# NyanTimer-v5.net
KiCad netlist of a schematic drawn in EAGLE
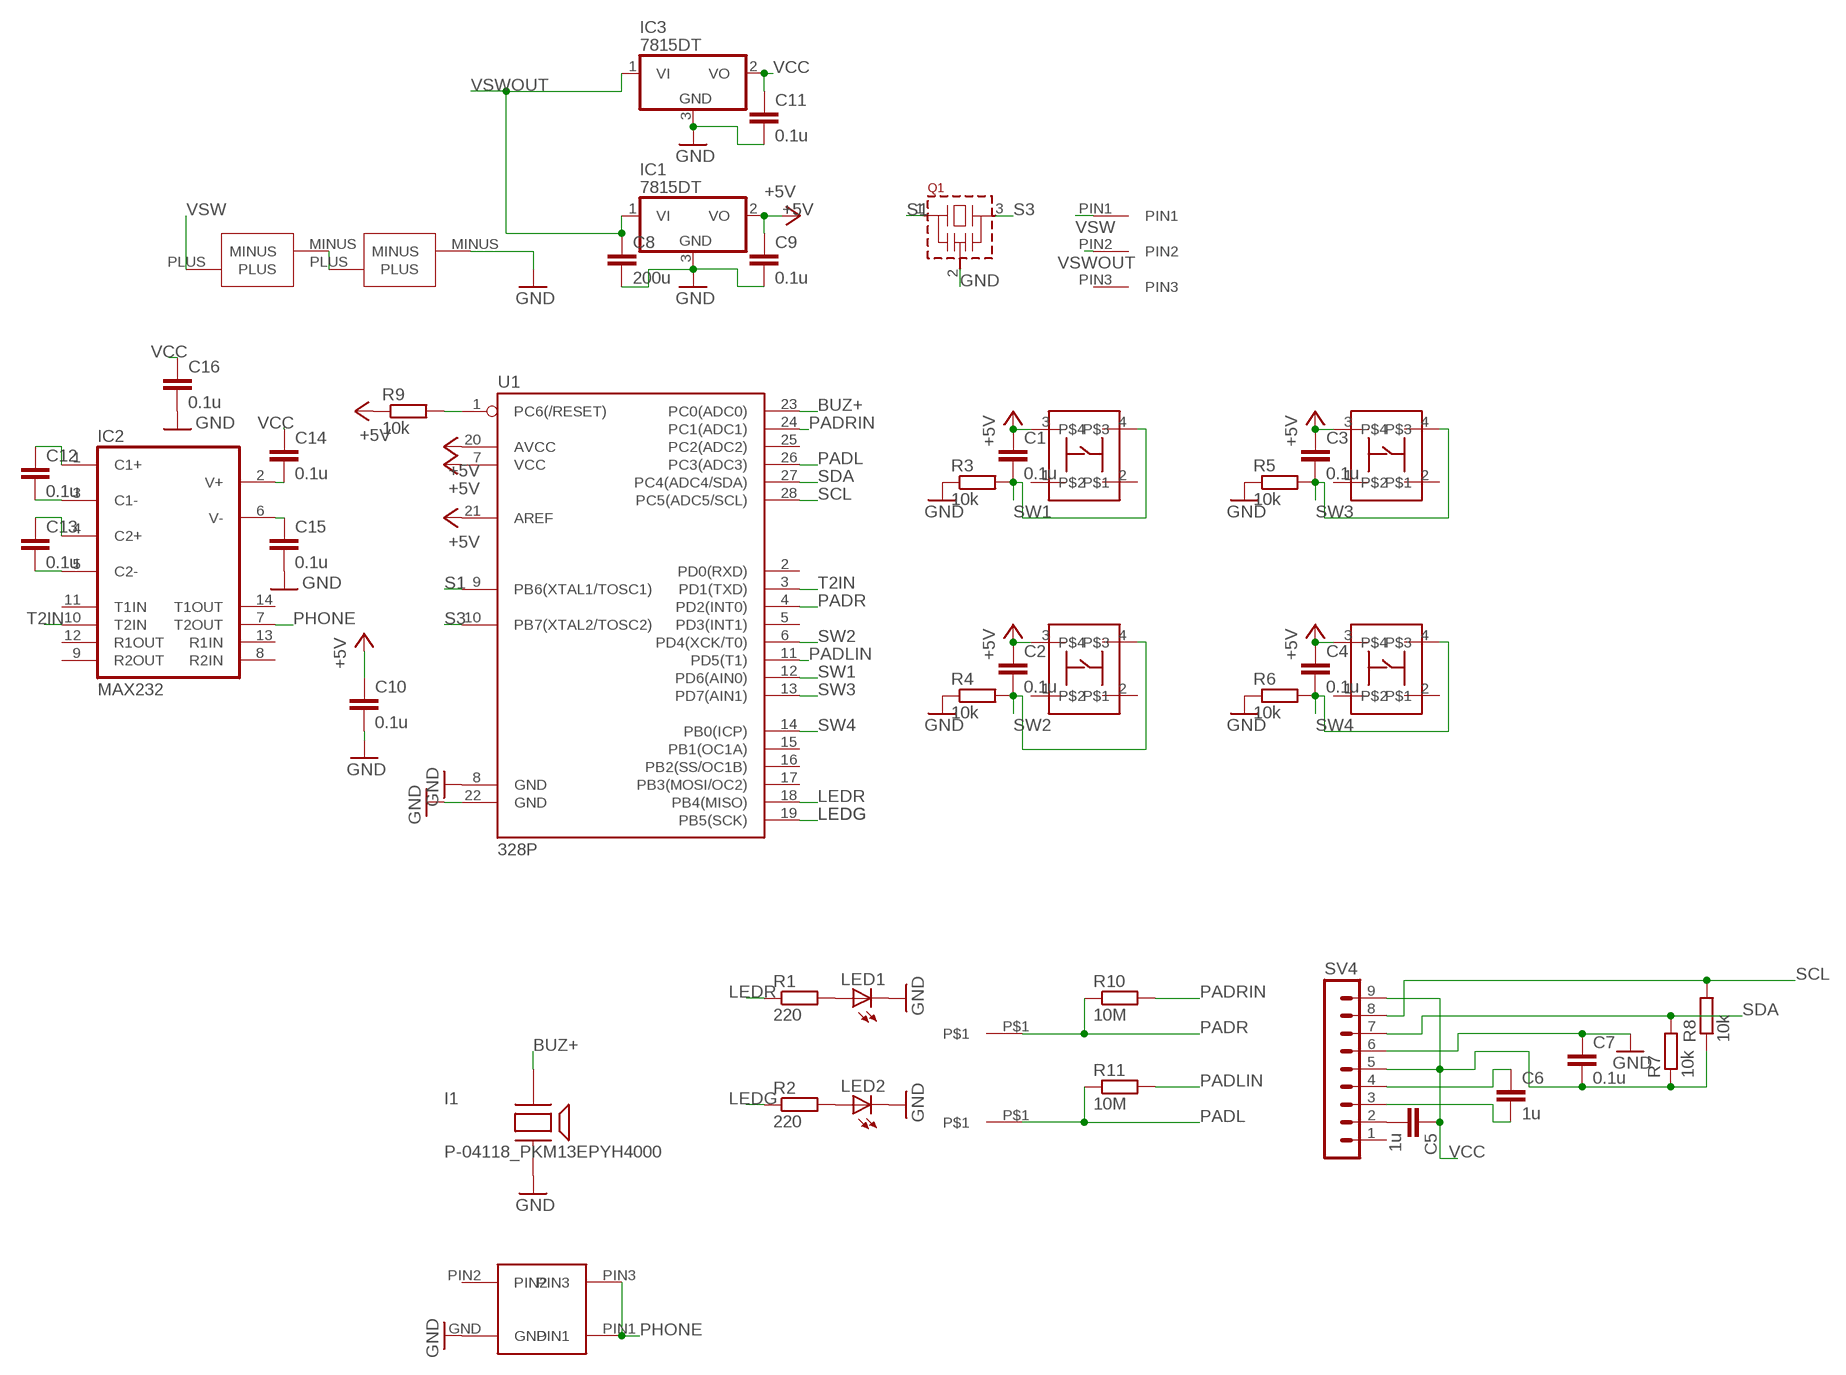
[diagram p0: schematic, sheet 1]

(export (version "E")
  (design (tool "Eeschema 10.0.6"))
  (components
    (comp (ref "BT1")
      (value "AKIZUKI_CR2032")
      (footprint "eagle-import:AKIZUKI_CR2032")
      (libsource (lib "eagle-import") (part "AKIZUKI_CR2032"))
    )
    (comp (ref "BT2")
      (value "AKIZUKI_CR2032")
      (footprint "eagle-import:AKIZUKI_CR2032")
      (libsource (lib "eagle-import") (part "AKIZUKI_CR2032"))
    )
    (comp (ref "C1")
      (value "0.1u")
      (footprint "eagle-import:C025-024X044")
      (libsource (lib "eagle-import") (part "C-EU025-024X044"))
    )
    (comp (ref "C2")
      (value "0.1u")
      (footprint "eagle-import:C025-024X044")
      (libsource (lib "eagle-import") (part "C-EU025-024X044"))
    )
    (comp (ref "C3")
      (value "0.1u")
      (footprint "eagle-import:C025-024X044")
      (libsource (lib "eagle-import") (part "C-EU025-024X044"))
    )
    (comp (ref "C4")
      (value "0.1u")
      (footprint "eagle-import:C025-024X044")
      (libsource (lib "eagle-import") (part "C-EU025-024X044"))
    )
    (comp (ref "C5")
      (value "1u")
      (footprint "eagle-import:C025-024X044")
      (libsource (lib "eagle-import") (part "C-EU025-024X044"))
    )
    (comp (ref "C6")
      (value "1u")
      (footprint "eagle-import:C025-024X044")
      (libsource (lib "eagle-import") (part "C-EU025-024X044"))
    )
    (comp (ref "C7")
      (value "0.1u")
      (footprint "eagle-import:C025-024X044")
      (libsource (lib "eagle-import") (part "C-EU025-024X044"))
    )
    (comp (ref "C8")
      (value "200u")
      (footprint "eagle-import:C025-024X044")
      (libsource (lib "eagle-import") (part "C-EU025-024X044"))
    )
    (comp (ref "C9")
      (value "0.1u")
      (footprint "eagle-import:C025-024X044")
      (libsource (lib "eagle-import") (part "C-EU025-024X044"))
    )
    (comp (ref "C10")
      (value "0.1u")
      (footprint "eagle-import:C025-024X044")
      (libsource (lib "eagle-import") (part "C-EU025-024X044"))
    )
    (comp (ref "C11")
      (value "0.1u")
      (footprint "eagle-import:C025-024X044")
      (libsource (lib "eagle-import") (part "C-EU025-024X044"))
    )
    (comp (ref "C12")
      (value "0.1u")
      (footprint "eagle-import:C025-024X044")
      (libsource (lib "eagle-import") (part "C-EU025-024X044"))
    )
    (comp (ref "C13")
      (value "0.1u")
      (footprint "eagle-import:C025-024X044")
      (libsource (lib "eagle-import") (part "C-EU025-024X044"))
    )
    (comp (ref "C14")
      (value "0.1u")
      (footprint "eagle-import:C025-024X044")
      (libsource (lib "eagle-import") (part "C-EU025-024X044"))
    )
    (comp (ref "C15")
      (value "0.1u")
      (footprint "eagle-import:C025-024X044")
      (libsource (lib "eagle-import") (part "C-EU025-024X044"))
    )
    (comp (ref "C16")
      (value "0.1u")
      (footprint "eagle-import:C025-024X044")
      (libsource (lib "eagle-import") (part "C-EU025-024X044"))
    )
    (comp (ref "CONNECTOR1")
      (value "TACT_SWITCH")
      (footprint "eagle-import:TACT_SWITCH")
      (libsource (lib "eagle-import") (part "TACT_SWITCH"))
    )
    (comp (ref "CONNECTOR2")
      (value "TACT_SWITCH")
      (footprint "eagle-import:TACT_SWITCH")
      (libsource (lib "eagle-import") (part "TACT_SWITCH"))
    )
    (comp (ref "CONNECTOR3")
      (value "TACT_SWITCH")
      (footprint "eagle-import:TACT_SWITCH")
      (libsource (lib "eagle-import") (part "TACT_SWITCH"))
    )
    (comp (ref "CONNECTOR4")
      (value "TACT_SWITCH")
      (footprint "eagle-import:TACT_SWITCH")
      (libsource (lib "eagle-import") (part "TACT_SWITCH"))
    )
    (comp (ref "I1")
      (value "P-04118_PKM13EPYH4000")
      (footprint "eagle-import:PKM13EPYH4000")
      (libsource (lib "eagle-import") (part "P-04118_PKM13EPYH4000"))
    )
    (comp (ref "IC1")
      (value "7815DT")
      (footprint "eagle-import:TO252")
      (libsource (lib "eagle-import") (part "78DT15"))
    )
    (comp (ref "IC2")
      (value "MAX232")
      (footprint "eagle-import:DIL16")
      (fields (field (name "MF") "MAXIM") (field (name "MPN") "MAX232ACPE+"))
      (libsource (lib "eagle-import") (part "MAX232"))
    )
    (comp (ref "IC3")
      (value "7815DT")
      (footprint "eagle-import:TO252")
      (libsource (lib "eagle-import") (part "78DT15"))
    )
    (comp (ref "LED1")
      (value "LED3MM")
      (footprint "eagle-import:LED3MM")
      (libsource (lib "eagle-import") (part "LED3MM"))
    )
    (comp (ref "LED2")
      (value "LED3MM")
      (footprint "eagle-import:LED3MM")
      (libsource (lib "eagle-import") (part "LED3MM"))
    )
    (comp (ref "PHN1")
      (value "PHONE")
      (footprint "eagle-import:PHONE")
      (libsource (lib "eagle-import") (part "PHONE"))
    )
    (comp (ref "PIN1")
      (value "1PINHEAD")
      (footprint "eagle-import:1PINHEAD")
      (libsource (lib "eagle-import") (part "1PINHEAD"))
    )
    (comp (ref "PIN2")
      (value "1PINHEAD")
      (footprint "eagle-import:1PINHEAD")
      (libsource (lib "eagle-import") (part "1PINHEAD"))
    )
    (comp (ref "Q1")
      (value "CSTLA_T")
      (footprint "eagle-import:CSTLA_T")
      (libsource (lib "eagle-import") (part "CSTLA_T"))
    )
    (comp (ref "R1")
      (value "220")
      (footprint "eagle-import:0207_10")
      (libsource (lib "eagle-import") (part "R-EU_0207/10"))
    )
    (comp (ref "R2")
      (value "220")
      (footprint "eagle-import:0207_10")
      (libsource (lib "eagle-import") (part "R-EU_0207/10"))
    )
    (comp (ref "R3")
      (value "10k")
      (footprint "eagle-import:0207_10")
      (libsource (lib "eagle-import") (part "R-EU_0207/10"))
    )
    (comp (ref "R4")
      (value "10k")
      (footprint "eagle-import:0207_10")
      (libsource (lib "eagle-import") (part "R-EU_0207/10"))
    )
    (comp (ref "R5")
      (value "10k")
      (footprint "eagle-import:0207_10")
      (libsource (lib "eagle-import") (part "R-EU_0207/10"))
    )
    (comp (ref "R6")
      (value "10k")
      (footprint "eagle-import:0207_10")
      (libsource (lib "eagle-import") (part "R-EU_0207/10"))
    )
    (comp (ref "R7")
      (value "10k")
      (footprint "eagle-import:0207_10")
      (libsource (lib "eagle-import") (part "R-EU_0207/10"))
    )
    (comp (ref "R8")
      (value "10k")
      (footprint "eagle-import:0207_10")
      (libsource (lib "eagle-import") (part "R-EU_0207/10"))
    )
    (comp (ref "R9")
      (value "10k")
      (footprint "eagle-import:0207_10")
      (libsource (lib "eagle-import") (part "R-EU_0207/10"))
    )
    (comp (ref "R10")
      (value "10M")
      (footprint "eagle-import:0207_10")
      (libsource (lib "eagle-import") (part "R-EU_0207/10"))
    )
    (comp (ref "R11")
      (value "10M")
      (footprint "eagle-import:0207_10")
      (libsource (lib "eagle-import") (part "R-EU_0207/10"))
    )
    (comp (ref "SV4")
      (value "MA09-1")
      (footprint "eagle-import:MA09-1")
      (libsource (lib "eagle-import") (part "MA09-1"))
    )
    (comp (ref "SW1")
      (value "AKIZUKI_SWITCH")
      (footprint "eagle-import:AKIZUKI_SWITCH")
      (libsource (lib "eagle-import") (part "AKIZUKI_SWITCH"))
    )
    (comp (ref "U1")
      (value "328P")
      (footprint "eagle-import:DIP28")
      (libsource (lib "eagle-import") (part "ATMEGA328P_PDIP"))
    )
  )
  (nets
    (net (code "1") (name "+5V") (class "Default")
      (node (ref "C1") (pin "1") (pinfunction "1_1") (pintype "passive"))
      (node (ref "C10") (pin "1") (pinfunction "1_1") (pintype "passive"))
      (node (ref "C2") (pin "1") (pinfunction "1_1") (pintype "passive"))
      (node (ref "C3") (pin "1") (pinfunction "1_1") (pintype "passive"))
      (node (ref "C4") (pin "1") (pinfunction "1_1") (pintype "passive"))
      (node (ref "C9") (pin "1") (pinfunction "1_1") (pintype "passive"))
      (node (ref "CONNECTOR1") (pin "3") (pinfunction "P$3_3") (pintype "bidirectional"))
      (node (ref "CONNECTOR2") (pin "3") (pinfunction "P$3_3") (pintype "bidirectional"))
      (node (ref "CONNECTOR3") (pin "3") (pinfunction "P$3_3") (pintype "bidirectional"))
      (node (ref "CONNECTOR4") (pin "3") (pinfunction "P$3_3") (pintype "bidirectional"))
      (node (ref "IC1") (pin "2") (pinfunction "VO_2") (pintype "passive"))
      (node (ref "R9") (pin "1") (pinfunction "1_1") (pintype "passive"))
      (node (ref "U1") (pin "20") (pinfunction "AVCC_20") (pintype "bidirectional"))
      (node (ref "U1") (pin "21") (pinfunction "AREF_21") (pintype "bidirectional"))
      (node (ref "U1") (pin "7") (pinfunction "VCC_7") (pintype "bidirectional"))
    )
    (net (code "2") (name "/BUZ+") (class "Default")
      (node (ref "I1") (pin "1") (pinfunction "1_1") (pintype "bidirectional"))
      (node (ref "U1") (pin "23") (pinfunction "PC0(ADC0)_23") (pintype "bidirectional"))
    )
    (net (code "3") (name "/LEDG") (class "Default")
      (node (ref "R2") (pin "1") (pinfunction "1_1") (pintype "passive"))
      (node (ref "U1") (pin "19") (pinfunction "PB5(SCK)_19") (pintype "bidirectional"))
    )
    (net (code "4") (name "/LEDR") (class "Default")
      (node (ref "R1") (pin "1") (pinfunction "1_1") (pintype "passive"))
      (node (ref "U1") (pin "18") (pinfunction "PB4(MISO)_18") (pintype "bidirectional"))
    )
    (net (code "5") (name "/PADL") (class "Default")
      (node (ref "PIN1") (pin "P$1") (pinfunction "P$1_P$1") (pintype "bidirectional"))
      (node (ref "R11") (pin "1") (pinfunction "1_1") (pintype "passive"))
      (node (ref "U1") (pin "26") (pinfunction "PC3(ADC3)_26") (pintype "bidirectional"))
    )
    (net (code "6") (name "/PADLIN") (class "Default")
      (node (ref "R11") (pin "2") (pinfunction "2_2") (pintype "passive"))
      (node (ref "U1") (pin "11") (pinfunction "PD5(T1)_11") (pintype "bidirectional"))
    )
    (net (code "7") (name "/PADR") (class "Default")
      (node (ref "PIN2") (pin "P$1") (pinfunction "P$1_P$1") (pintype "bidirectional"))
      (node (ref "R10") (pin "1") (pinfunction "1_1") (pintype "passive"))
      (node (ref "U1") (pin "4") (pinfunction "PD2(INT0)_4") (pintype "bidirectional"))
    )
    (net (code "8") (name "/PADRIN") (class "Default")
      (node (ref "R10") (pin "2") (pinfunction "2_2") (pintype "passive"))
      (node (ref "U1") (pin "24") (pinfunction "PC1(ADC1)_24") (pintype "bidirectional"))
    )
    (net (code "9") (name "/PHONE") (class "Default")
      (node (ref "IC2") (pin "7") (pinfunction "T2OUT_7") (pintype "output"))
      (node (ref "PHN1") (pin "PIN1") (pinfunction "PIN1_PIN1") (pintype "bidirectional"))
      (node (ref "PHN1") (pin "PIN3") (pinfunction "PIN3_PIN3") (pintype "bidirectional"))
    )
    (net (code "10") (name "/S1") (class "Default")
      (node (ref "Q1") (pin "1") (pinfunction "1_1") (pintype "output"))
      (node (ref "U1") (pin "9") (pinfunction "PB6(XTAL1/TOSC1)_9") (pintype "bidirectional"))
    )
    (net (code "11") (name "/S3") (class "Default")
      (node (ref "Q1") (pin "3") (pinfunction "3_3") (pintype "input"))
      (node (ref "U1") (pin "10") (pinfunction "PB7(XTAL2/TOSC2)_10") (pintype "bidirectional"))
    )
    (net (code "12") (name "/SCL") (class "Default")
      (node (ref "R8") (pin "2") (pinfunction "2_2") (pintype "passive"))
      (node (ref "SV4") (pin "8") (pinfunction "8_8") (pintype "passive"))
      (node (ref "U1") (pin "28") (pinfunction "PC5(ADC5/SCL)_28") (pintype "bidirectional"))
    )
    (net (code "13") (name "/SDA") (class "Default")
      (node (ref "R7") (pin "2") (pinfunction "2_2") (pintype "passive"))
      (node (ref "SV4") (pin "7") (pinfunction "7_7") (pintype "passive"))
      (node (ref "U1") (pin "27") (pinfunction "PC4(ADC4/SDA)_27") (pintype "bidirectional"))
    )
    (net (code "14") (name "/SW1") (class "Default")
      (node (ref "C1") (pin "2") (pinfunction "2_2") (pintype "passive"))
      (node (ref "CONNECTOR1") (pin "4") (pinfunction "P$4_4") (pintype "bidirectional"))
      (node (ref "R3") (pin "2") (pinfunction "2_2") (pintype "passive"))
      (node (ref "U1") (pin "12") (pinfunction "PD6(AIN0)_12") (pintype "bidirectional"))
    )
    (net (code "15") (name "/SW2") (class "Default")
      (node (ref "C2") (pin "2") (pinfunction "2_2") (pintype "passive"))
      (node (ref "CONNECTOR2") (pin "4") (pinfunction "P$4_4") (pintype "bidirectional"))
      (node (ref "R4") (pin "2") (pinfunction "2_2") (pintype "passive"))
      (node (ref "U1") (pin "6") (pinfunction "PD4(XCK/T0)_6") (pintype "bidirectional"))
    )
    (net (code "16") (name "/SW3") (class "Default")
      (node (ref "C3") (pin "2") (pinfunction "2_2") (pintype "passive"))
      (node (ref "CONNECTOR3") (pin "4") (pinfunction "P$4_4") (pintype "bidirectional"))
      (node (ref "R5") (pin "2") (pinfunction "2_2") (pintype "passive"))
      (node (ref "U1") (pin "13") (pinfunction "PD7(AIN1)_13") (pintype "bidirectional"))
    )
    (net (code "17") (name "/SW4") (class "Default")
      (node (ref "C4") (pin "2") (pinfunction "2_2") (pintype "passive"))
      (node (ref "CONNECTOR4") (pin "4") (pinfunction "P$4_4") (pintype "bidirectional"))
      (node (ref "R6") (pin "2") (pinfunction "2_2") (pintype "passive"))
      (node (ref "U1") (pin "14") (pinfunction "PB0(ICP)_14") (pintype "bidirectional"))
    )
    (net (code "18") (name "/T2IN") (class "Default")
      (node (ref "IC2") (pin "10") (pinfunction "T2IN_10") (pintype "input"))
      (node (ref "U1") (pin "3") (pinfunction "PD1(TXD)_3") (pintype "bidirectional"))
    )
    (net (code "19") (name "/VCC") (class "Default")
      (node (ref "C11") (pin "1") (pinfunction "1_1") (pintype "passive"))
      (node (ref "C14") (pin "1") (pinfunction "1_1") (pintype "passive"))
      (node (ref "C16") (pin "1") (pinfunction "1_1") (pintype "passive"))
      (node (ref "C5") (pin "1") (pinfunction "1_1") (pintype "passive"))
      (node (ref "C7") (pin "2") (pinfunction "2_2") (pintype "passive"))
      (node (ref "IC3") (pin "2") (pinfunction "VO_2") (pintype "passive"))
      (node (ref "R7") (pin "1") (pinfunction "1_1") (pintype "passive"))
      (node (ref "R8") (pin "1") (pinfunction "1_1") (pintype "passive"))
      (node (ref "SV4") (pin "5") (pinfunction "5_5") (pintype "passive"))
      (node (ref "SV4") (pin "9") (pinfunction "9_9") (pintype "passive"))
    )
    (net (code "20") (name "/VSW") (class "Default")
      (node (ref "BT1") (pin "PLUS") (pinfunction "PLUS_PLUS") (pintype "bidirectional"))
      (node (ref "SW1") (pin "PIN1") (pinfunction "PIN1_PIN1") (pintype "bidirectional"))
    )
    (net (code "21") (name "/VSWOUT") (class "Default")
      (node (ref "C8") (pin "1") (pinfunction "1_1") (pintype "passive"))
      (node (ref "IC1") (pin "1") (pinfunction "VI_1") (pintype "input"))
      (node (ref "IC3") (pin "1") (pinfunction "VI_1") (pintype "input"))
      (node (ref "SW1") (pin "PIN2") (pinfunction "PIN2_PIN2") (pintype "bidirectional"))
    )
    (net (code "22") (name "GND") (class "Default")
      (node (ref "BT2") (pin "MINUS") (pinfunction "MINUS_MINUS") (pintype "bidirectional"))
      (node (ref "C10") (pin "2") (pinfunction "2_2") (pintype "passive"))
      (node (ref "C11") (pin "2") (pinfunction "2_2") (pintype "passive"))
      (node (ref "C15") (pin "2") (pinfunction "2_2") (pintype "passive"))
      (node (ref "C16") (pin "2") (pinfunction "2_2") (pintype "passive"))
      (node (ref "C7") (pin "1") (pinfunction "1_1") (pintype "passive"))
      (node (ref "C8") (pin "2") (pinfunction "2_2") (pintype "passive"))
      (node (ref "C9") (pin "2") (pinfunction "2_2") (pintype "passive"))
      (node (ref "I1") (pin "2") (pinfunction "2_2") (pintype "bidirectional"))
      (node (ref "IC1") (pin "3") (pinfunction "GND_3") (pintype "passive"))
      (node (ref "IC3") (pin "3") (pinfunction "GND_3") (pintype "passive"))
      (node (ref "LED1") (pin "K") (pinfunction "C_K") (pintype "passive"))
      (node (ref "LED2") (pin "K") (pinfunction "C_K") (pintype "passive"))
      (node (ref "PHN1") (pin "GND") (pinfunction "GND_GND") (pintype "bidirectional"))
      (node (ref "Q1") (pin "2") (pinfunction "VSS_2") (pintype "power_in"))
      (node (ref "R3") (pin "1") (pinfunction "1_1") (pintype "passive"))
      (node (ref "R4") (pin "1") (pinfunction "1_1") (pintype "passive"))
      (node (ref "R5") (pin "1") (pinfunction "1_1") (pintype "passive"))
      (node (ref "R6") (pin "1") (pinfunction "1_1") (pintype "passive"))
      (node (ref "SV4") (pin "6") (pinfunction "6_6") (pintype "passive"))
      (node (ref "U1") (pin "22") (pinfunction "GND_22") (pintype "bidirectional"))
      (node (ref "U1") (pin "8") (pinfunction "GND_8") (pintype "bidirectional"))
    )
    (net (code "23") (name "Net-(BT1-PadMINUS)") (class "Default")
      (node (ref "BT1") (pin "MINUS") (pinfunction "MINUS_MINUS") (pintype "bidirectional"))
      (node (ref "BT2") (pin "PLUS") (pinfunction "PLUS_PLUS") (pintype "bidirectional"))
    )
    (net (code "24") (name "Net-(C5-Pad2)") (class "Default")
      (node (ref "C5") (pin "2") (pinfunction "2_2") (pintype "passive"))
      (node (ref "SV4") (pin "2") (pinfunction "2_2") (pintype "passive"))
    )
    (net (code "25") (name "Net-(C6-Pad1)") (class "Default")
      (node (ref "C6") (pin "1") (pinfunction "1_1") (pintype "passive"))
      (node (ref "SV4") (pin "4") (pinfunction "4_4") (pintype "passive"))
    )
    (net (code "26") (name "Net-(C6-Pad2)") (class "Default")
      (node (ref "C6") (pin "2") (pinfunction "2_2") (pintype "passive"))
      (node (ref "SV4") (pin "3") (pinfunction "3_3") (pintype "passive"))
    )
    (net (code "27") (name "Net-(IC2A-C1+)") (class "Default")
      (node (ref "C12") (pin "1") (pinfunction "1_1") (pintype "passive"))
      (node (ref "IC2") (pin "1") (pinfunction "C1+_1") (pintype "bidirectional"))
    )
    (net (code "28") (name "Net-(IC2A-C1-)") (class "Default")
      (node (ref "C12") (pin "2") (pinfunction "2_2") (pintype "passive"))
      (node (ref "IC2") (pin "3") (pinfunction "C1-_3") (pintype "bidirectional"))
    )
    (net (code "29") (name "Net-(IC2A-C2+)") (class "Default")
      (node (ref "C13") (pin "1") (pinfunction "1_1") (pintype "passive"))
      (node (ref "IC2") (pin "4") (pinfunction "C2+_4") (pintype "bidirectional"))
    )
    (net (code "30") (name "Net-(IC2A-C2-)") (class "Default")
      (node (ref "C13") (pin "2") (pinfunction "2_2") (pintype "passive"))
      (node (ref "IC2") (pin "5") (pinfunction "C2-_5") (pintype "bidirectional"))
    )
    (net (code "31") (name "Net-(IC2A-V+)") (class "Default")
      (node (ref "C14") (pin "2") (pinfunction "2_2") (pintype "passive"))
      (node (ref "IC2") (pin "2") (pinfunction "V+_2") (pintype "bidirectional"))
    )
    (net (code "32") (name "Net-(IC2A-V-)") (class "Default")
      (node (ref "C15") (pin "1") (pinfunction "1_1") (pintype "passive"))
      (node (ref "IC2") (pin "6") (pinfunction "V-_6") (pintype "bidirectional"))
    )
    (net (code "33") (name "Net-(LED1-PadA)") (class "Default")
      (node (ref "LED1") (pin "A") (pinfunction "A_A") (pintype "passive"))
      (node (ref "R1") (pin "2") (pinfunction "2_2") (pintype "passive"))
    )
    (net (code "34") (name "Net-(LED2-PadA)") (class "Default")
      (node (ref "LED2") (pin "A") (pinfunction "A_A") (pintype "passive"))
      (node (ref "R2") (pin "2") (pinfunction "2_2") (pintype "passive"))
    )
    (net (code "35") (name "Net-(U1-PC6({slash}RESET))") (class "Default")
      (node (ref "R9") (pin "2") (pinfunction "2_2") (pintype "passive"))
      (node (ref "U1") (pin "1") (pinfunction "PC6(/RESET)_1") (pintype "bidirectional"))
    )
    (net (code "36") (name "unconnected-(CONNECTOR1-P$1-Pad1)") (class "Default")
      (node (ref "CONNECTOR1") (pin "1") (pinfunction "P$1_1") (pintype "bidirectional"))
    )
    (net (code "37") (name "unconnected-(CONNECTOR1-P$2-Pad2)") (class "Default")
      (node (ref "CONNECTOR1") (pin "2") (pinfunction "P$2_2") (pintype "bidirectional"))
    )
    (net (code "38") (name "unconnected-(CONNECTOR2-P$1-Pad1)") (class "Default")
      (node (ref "CONNECTOR2") (pin "1") (pinfunction "P$1_1") (pintype "bidirectional"))
    )
    (net (code "39") (name "unconnected-(CONNECTOR2-P$2-Pad2)") (class "Default")
      (node (ref "CONNECTOR2") (pin "2") (pinfunction "P$2_2") (pintype "bidirectional"))
    )
    (net (code "40") (name "unconnected-(CONNECTOR3-P$1-Pad1)") (class "Default")
      (node (ref "CONNECTOR3") (pin "1") (pinfunction "P$1_1") (pintype "bidirectional"))
    )
    (net (code "41") (name "unconnected-(CONNECTOR3-P$2-Pad2)") (class "Default")
      (node (ref "CONNECTOR3") (pin "2") (pinfunction "P$2_2") (pintype "bidirectional"))
    )
    (net (code "42") (name "unconnected-(CONNECTOR4-P$1-Pad1)") (class "Default")
      (node (ref "CONNECTOR4") (pin "1") (pinfunction "P$1_1") (pintype "bidirectional"))
    )
    (net (code "43") (name "unconnected-(CONNECTOR4-P$2-Pad2)") (class "Default")
      (node (ref "CONNECTOR4") (pin "2") (pinfunction "P$2_2") (pintype "bidirectional"))
    )
    (net (code "44") (name "unconnected-(IC2A-R1IN-Pad13)") (class "Default")
      (node (ref "IC2") (pin "13") (pinfunction "R1IN_13") (pintype "input"))
    )
    (net (code "45") (name "unconnected-(IC2A-R1OUT-Pad12)") (class "Default")
      (node (ref "IC2") (pin "12") (pinfunction "R1OUT_12") (pintype "output"))
    )
    (net (code "46") (name "unconnected-(IC2A-R2IN-Pad8)") (class "Default")
      (node (ref "IC2") (pin "8") (pinfunction "R2IN_8") (pintype "input"))
    )
    (net (code "47") (name "unconnected-(IC2A-R2OUT-Pad9)") (class "Default")
      (node (ref "IC2") (pin "9") (pinfunction "R2OUT_9") (pintype "output"))
    )
    (net (code "48") (name "unconnected-(IC2A-T1IN-Pad11)") (class "Default")
      (node (ref "IC2") (pin "11") (pinfunction "T1IN_11") (pintype "input"))
    )
    (net (code "49") (name "unconnected-(IC2A-T1OUT-Pad14)") (class "Default")
      (node (ref "IC2") (pin "14") (pinfunction "T1OUT_14") (pintype "output"))
    )
    (net (code "50") (name "unconnected-(PHN1-PadPIN2)") (class "Default")
      (node (ref "PHN1") (pin "PIN2") (pinfunction "PIN2_PIN2") (pintype "bidirectional"))
    )
    (net (code "51") (name "unconnected-(SV4-Pad1)") (class "Default")
      (node (ref "SV4") (pin "1") (pinfunction "1_1") (pintype "passive"))
    )
    (net (code "52") (name "unconnected-(SW1-PadPIN3)") (class "Default")
      (node (ref "SW1") (pin "PIN3") (pinfunction "PIN3_PIN3") (pintype "bidirectional"))
    )
    (net (code "53") (name "unconnected-(U1-PB1(OC1A)-Pad15)") (class "Default")
      (node (ref "U1") (pin "15") (pinfunction "PB1(OC1A)_15") (pintype "bidirectional"))
    )
    (net (code "54") (name "unconnected-(U1-PB2(SS{slash}OC1B)-Pad16)") (class "Default")
      (node (ref "U1") (pin "16") (pinfunction "PB2(SS/OC1B)_16") (pintype "bidirectional"))
    )
    (net (code "55") (name "unconnected-(U1-PB3(MOSI{slash}OC2)-Pad17)") (class "Default")
      (node (ref "U1") (pin "17") (pinfunction "PB3(MOSI/OC2)_17") (pintype "bidirectional"))
    )
    (net (code "56") (name "unconnected-(U1-PC2(ADC2)-Pad25)") (class "Default")
      (node (ref "U1") (pin "25") (pinfunction "PC2(ADC2)_25") (pintype "bidirectional"))
    )
    (net (code "57") (name "unconnected-(U1-PD0(RXD)-Pad2)") (class "Default")
      (node (ref "U1") (pin "2") (pinfunction "PD0(RXD)_2") (pintype "bidirectional"))
    )
    (net (code "58") (name "unconnected-(U1-PD3(INT1)-Pad5)") (class "Default")
      (node (ref "U1") (pin "5") (pinfunction "PD3(INT1)_5") (pintype "bidirectional"))
    )
  )
)
